# PrismTricoreVCO.net
KiCad netlist of a schematic drawn in EAGLE
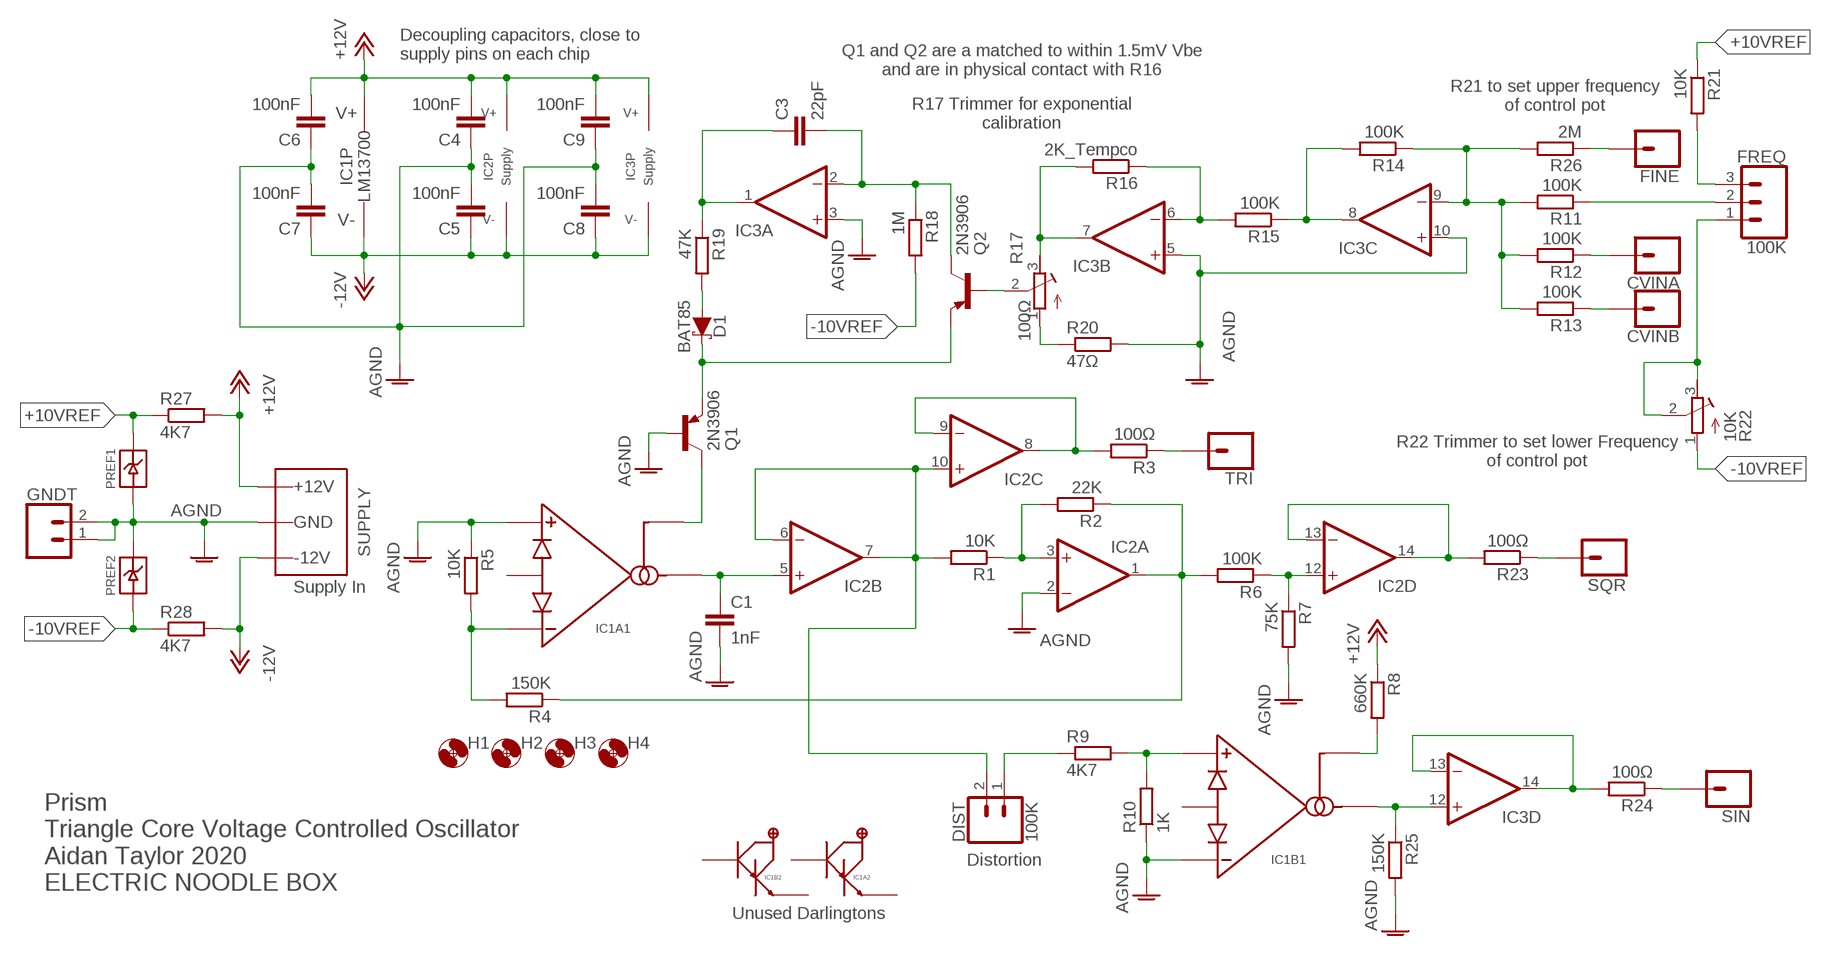
[diagram p0: schematic, sheet 1]

(export (version "E")
  (design (tool "Eeschema 10.0.6"))
  (components
    (comp (ref "C1")
      (value "1nF")
      (footprint "eagle-import:C050-025X075")
      (libsource (lib "eagle-import") (part "C-EU050-025X075"))
    )
    (comp (ref "C3")
      (value "22pF")
      (footprint "eagle-import:C050-025X075")
      (libsource (lib "eagle-import") (part "C-EU050-025X075"))
    )
    (comp (ref "C4")
      (value "100nF")
      (footprint "eagle-import:C050-025X075")
      (libsource (lib "eagle-import") (part "C-EU050-025X075"))
    )
    (comp (ref "C5")
      (value "100nF")
      (footprint "eagle-import:C050-025X075")
      (libsource (lib "eagle-import") (part "C-EU050-025X075"))
    )
    (comp (ref "C6")
      (value "100nF")
      (footprint "eagle-import:C050-025X075")
      (libsource (lib "eagle-import") (part "C-EU050-025X075"))
    )
    (comp (ref "C7")
      (value "100nF")
      (footprint "eagle-import:C050-025X075")
      (libsource (lib "eagle-import") (part "C-EU050-025X075"))
    )
    (comp (ref "C8")
      (value "100nF")
      (footprint "eagle-import:C050-025X075")
      (libsource (lib "eagle-import") (part "C-EU050-025X075"))
    )
    (comp (ref "C9")
      (value "100nF")
      (footprint "eagle-import:C050-025X075")
      (libsource (lib "eagle-import") (part "C-EU050-025X075"))
    )
    (comp (ref "CVINA")
      (value "1XWIREPAD")
      (footprint "eagle-import:1X01")
      (libsource (lib "eagle-import") (part "1XWIREPAD"))
    )
    (comp (ref "CVINB")
      (value "1XWIREPAD")
      (footprint "eagle-import:1X01")
      (libsource (lib "eagle-import") (part "1XWIREPAD"))
    )
    (comp (ref "D1")
      (value "BAT85")
      (footprint "eagle-import:DO35-7")
      (libsource (lib "eagle-import") (part "SCHOTTKY_DO35"))
    )
    (comp (ref "DIST")
      (value "100K")
      (footprint "eagle-import:1X02")
      (libsource (lib "eagle-import") (part "2XWIREPAD"))
    )
    (comp (ref "FINE")
      (value "1XWIREPAD")
      (footprint "eagle-import:1X01")
      (libsource (lib "eagle-import") (part "1XWIREPAD"))
    )
    (comp (ref "FREQ")
      (value "100K")
      (footprint "eagle-import:1X03")
      (libsource (lib "eagle-import") (part "3XWIREPAD"))
    )
    (comp (ref "GNDT")
      (value "2XWIREPAD")
      (footprint "eagle-import:1X02")
      (libsource (lib "eagle-import") (part "2XWIREPAD"))
    )
    (comp (ref "H1")
      (value "MOUNT-HOLE3.2")
      (footprint "eagle-import:3,2")
      (libsource (lib "eagle-import") (part "MOUNT-HOLE3.2"))
    )
    (comp (ref "H2")
      (value "MOUNT-HOLE3.2")
      (footprint "eagle-import:3,2")
      (libsource (lib "eagle-import") (part "MOUNT-HOLE3.2"))
    )
    (comp (ref "H3")
      (value "MOUNT-HOLE3.2")
      (footprint "eagle-import:3,2")
      (libsource (lib "eagle-import") (part "MOUNT-HOLE3.2"))
    )
    (comp (ref "H4")
      (value "MOUNT-HOLE3.2")
      (footprint "eagle-import:3,2")
      (libsource (lib "eagle-import") (part "MOUNT-HOLE3.2"))
    )
    (comp (ref "IC1")
      (value "LM13700DIL")
      (footprint "eagle-import:DIL16")
      (libsource (lib "eagle-import") (part "LM13700DIL"))
    )
    (comp (ref "IC2")
      (value "TL0X4DIL")
      (footprint "eagle-import:DIL14")
      (libsource (lib "eagle-import") (part "TL0X4DIL"))
    )
    (comp (ref "IC3")
      (value "TL0X4DIL")
      (footprint "eagle-import:DIL14")
      (libsource (lib "eagle-import") (part "TL0X4DIL"))
    )
    (comp (ref "PREF1")
      (value "LM4040TH")
      (footprint "eagle-import:TO92")
      (libsource (lib "eagle-import") (part "LM4040TH"))
    )
    (comp (ref "PREF2")
      (value "LM4040TH")
      (footprint "eagle-import:TO92")
      (libsource (lib "eagle-import") (part "LM4040TH"))
    )
    (comp (ref "Q1")
      (value "2N3906")
      (footprint "eagle-import:TO92")
      (libsource (lib "eagle-import") (part "2N3906"))
    )
    (comp (ref "Q2")
      (value "2N3906")
      (footprint "eagle-import:TO92")
      (libsource (lib "eagle-import") (part "2N3906"))
    )
    (comp (ref "R1")
      (value "10K")
      (footprint "eagle-import:0207_10")
      (libsource (lib "eagle-import") (part "R-EU_0207/10"))
    )
    (comp (ref "R2")
      (value "22K")
      (footprint "eagle-import:0207_10")
      (libsource (lib "eagle-import") (part "R-EU_0207/10"))
    )
    (comp (ref "R3")
      (value "100Ω")
      (footprint "eagle-import:0207_10")
      (libsource (lib "eagle-import") (part "R-EU_0207/10"))
    )
    (comp (ref "R4")
      (value "150K")
      (footprint "eagle-import:0207_10")
      (libsource (lib "eagle-import") (part "R-EU_0207/10"))
    )
    (comp (ref "R5")
      (value "10K")
      (footprint "eagle-import:0207_10")
      (libsource (lib "eagle-import") (part "R-EU_0207/10"))
    )
    (comp (ref "R6")
      (value "100K")
      (footprint "eagle-import:0207_10")
      (libsource (lib "eagle-import") (part "R-EU_0207/10"))
    )
    (comp (ref "R7")
      (value "75K")
      (footprint "eagle-import:0207_10")
      (libsource (lib "eagle-import") (part "R-EU_0207/10"))
    )
    (comp (ref "R8")
      (value "660K")
      (footprint "eagle-import:0207_10")
      (libsource (lib "eagle-import") (part "R-EU_0207/10"))
    )
    (comp (ref "R9")
      (value "4K7")
      (footprint "eagle-import:0207_10")
      (libsource (lib "eagle-import") (part "R-EU_0207/10"))
    )
    (comp (ref "R10")
      (value "1K")
      (footprint "eagle-import:0207_10")
      (libsource (lib "eagle-import") (part "R-EU_0207/10"))
    )
    (comp (ref "R11")
      (value "100K")
      (footprint "eagle-import:0207_10")
      (libsource (lib "eagle-import") (part "R-EU_0207/10"))
    )
    (comp (ref "R12")
      (value "100K")
      (footprint "eagle-import:0207_10")
      (libsource (lib "eagle-import") (part "R-EU_0207/10"))
    )
    (comp (ref "R13")
      (value "100K")
      (footprint "eagle-import:0207_10")
      (libsource (lib "eagle-import") (part "R-EU_0207/10"))
    )
    (comp (ref "R14")
      (value "100K")
      (footprint "eagle-import:0207_10")
      (libsource (lib "eagle-import") (part "R-EU_0207/10"))
    )
    (comp (ref "R15")
      (value "100K")
      (footprint "eagle-import:0207_10")
      (libsource (lib "eagle-import") (part "R-EU_0207/10"))
    )
    (comp (ref "R16")
      (value "2K_Tempco")
      (footprint "eagle-import:0207_10")
      (libsource (lib "eagle-import") (part "R-EU_0207/10"))
    )
    (comp (ref "R17")
      (value "100Ω")
      (footprint "eagle-import:RTRIM3296W")
      (libsource (lib "eagle-import") (part "R-TRIMM3296W"))
    )
    (comp (ref "R18")
      (value "1M")
      (footprint "eagle-import:0207_10")
      (libsource (lib "eagle-import") (part "R-EU_0207/10"))
    )
    (comp (ref "R19")
      (value "47K")
      (footprint "eagle-import:0207_10")
      (libsource (lib "eagle-import") (part "R-EU_0207/10"))
    )
    (comp (ref "R20")
      (value "47Ω")
      (footprint "eagle-import:0207_10")
      (libsource (lib "eagle-import") (part "R-EU_0207/10"))
    )
    (comp (ref "R21")
      (value "10K")
      (footprint "eagle-import:0207_10")
      (libsource (lib "eagle-import") (part "R-EU_0207/10"))
    )
    (comp (ref "R22")
      (value "10K")
      (footprint "eagle-import:RTRIM3296W")
      (libsource (lib "eagle-import") (part "R-TRIMM3296W"))
    )
    (comp (ref "R23")
      (value "100Ω")
      (footprint "eagle-import:0207_10")
      (libsource (lib "eagle-import") (part "R-EU_0207/10"))
    )
    (comp (ref "R24")
      (value "100Ω")
      (footprint "eagle-import:0207_10")
      (libsource (lib "eagle-import") (part "R-EU_0207/10"))
    )
    (comp (ref "R25")
      (value "150K")
      (footprint "eagle-import:0207_10")
      (libsource (lib "eagle-import") (part "R-EU_0207/10"))
    )
    (comp (ref "R26")
      (value "2M")
      (footprint "eagle-import:0207_10")
      (libsource (lib "eagle-import") (part "R-EU_0207/10"))
    )
    (comp (ref "R27")
      (value "4K7")
      (footprint "eagle-import:0207_10")
      (libsource (lib "eagle-import") (part "R-EU_0207/10"))
    )
    (comp (ref "R28")
      (value "4K7")
      (footprint "eagle-import:0207_10")
      (libsource (lib "eagle-import") (part "R-EU_0207/10"))
    )
    (comp (ref "SIN")
      (value "1XWIREPAD")
      (footprint "eagle-import:1X01")
      (libsource (lib "eagle-import") (part "1XWIREPAD"))
    )
    (comp (ref "SQR")
      (value "1XWIREPAD")
      (footprint "eagle-import:1X01")
      (libsource (lib "eagle-import") (part "1XWIREPAD"))
    )
    (comp (ref "TRI")
      (value "1XWIREPAD")
      (footprint "eagle-import:1X01")
      (libsource (lib "eagle-import") (part "1XWIREPAD"))
    )
    (comp (ref "WP1")
      (value "COMBO_SUPPLY_HEADER")
      (footprint "eagle-import:COMBINED_POWER")
      (libsource (lib "eagle-import") (part "COMBO_SUPPLY_HEADER"))
    )
  )
  (nets
    (net (code "1") (name "+10VREF") (class "Default")
      (node (ref "PREF1") (pin "2") (pinfunction "CATHODE_2") (pintype "power_in"))
      (node (ref "R21") (pin "1") (pinfunction "1_1") (pintype "passive"))
      (node (ref "R27") (pin "1") (pinfunction "1_1") (pintype "passive"))
    )
    (net (code "2") (name "+12V") (class "Default")
      (node (ref "C4") (pin "2") (pinfunction "2_2") (pintype "passive"))
      (node (ref "C6") (pin "2") (pinfunction "2_2") (pintype "passive"))
      (node (ref "C9") (pin "2") (pinfunction "2_2") (pintype "passive"))
      (node (ref "IC1") (pin "11") (pinfunction "V+_11") (pintype "power_in"))
      (node (ref "IC2") (pin "4") (pinfunction "V+_4") (pintype "bidirectional"))
      (node (ref "IC3") (pin "4") (pinfunction "V+_4") (pintype "bidirectional"))
      (node (ref "R27") (pin "2") (pinfunction "2_2") (pintype "passive"))
      (node (ref "R8") (pin "1") (pinfunction "1_1") (pintype "passive"))
      (node (ref "WP1") (pin "V+1") (pinfunction "V++_V+1") (pintype "power_in"))
      (node (ref "WP1") (pin "V+2") (pinfunction "V++_V+2") (pintype "power_in"))
      (node (ref "WP1") (pin "V+3") (pinfunction "V++_V+3") (pintype "power_in"))
    )
    (net (code "3") (name "-10VREF") (class "Default")
      (node (ref "PREF2") (pin "3") (pinfunction "ANODE_3") (pintype "power_in"))
      (node (ref "R18") (pin "2") (pinfunction "2_2") (pintype "passive"))
      (node (ref "R22") (pin "1") (pinfunction "A_1") (pintype "passive"))
      (node (ref "R28") (pin "1") (pinfunction "1_1") (pintype "passive"))
    )
    (net (code "4") (name "-12V") (class "Default")
      (node (ref "C5") (pin "1") (pinfunction "1_1") (pintype "passive"))
      (node (ref "C7") (pin "1") (pinfunction "1_1") (pintype "passive"))
      (node (ref "C8") (pin "1") (pinfunction "1_1") (pintype "passive"))
      (node (ref "IC1") (pin "6") (pinfunction "V-_6") (pintype "power_in"))
      (node (ref "IC2") (pin "11") (pinfunction "V-_11") (pintype "bidirectional"))
      (node (ref "IC3") (pin "11") (pinfunction "V-_11") (pintype "bidirectional"))
      (node (ref "R28") (pin "2") (pinfunction "2_2") (pintype "passive"))
      (node (ref "WP1") (pin "V-1") (pinfunction "V--_V-1") (pintype "power_in"))
      (node (ref "WP1") (pin "V-2") (pinfunction "V--_V-2") (pintype "power_in"))
      (node (ref "WP1") (pin "V-3") (pinfunction "V--_V-3") (pintype "power_in"))
    )
    (net (code "5") (name "AGND") (class "Default")
      (node (ref "C1") (pin "2") (pinfunction "2_2") (pintype "passive"))
      (node (ref "C4") (pin "1") (pinfunction "1_1") (pintype "passive"))
      (node (ref "C5") (pin "2") (pinfunction "2_2") (pintype "passive"))
      (node (ref "C6") (pin "1") (pinfunction "1_1") (pintype "passive"))
      (node (ref "C7") (pin "2") (pinfunction "2_2") (pintype "passive"))
      (node (ref "C8") (pin "2") (pinfunction "2_2") (pintype "passive"))
      (node (ref "C9") (pin "1") (pinfunction "1_1") (pintype "passive"))
      (node (ref "GNDT") (pin "1") (pinfunction "1_1") (pintype "passive"))
      (node (ref "GNDT") (pin "2") (pinfunction "2_2") (pintype "passive"))
      (node (ref "IC1") (pin "13") (pinfunction "AMP-_13") (pintype "input"))
      (node (ref "IC1") (pin "3") (pinfunction "AMP+_3") (pintype "input"))
      (node (ref "IC2") (pin "2") (pinfunction "-IN_2") (pintype "input"))
      (node (ref "IC3") (pin "10") (pinfunction "+IN_10") (pintype "input"))
      (node (ref "IC3") (pin "3") (pinfunction "+IN_3") (pintype "input"))
      (node (ref "IC3") (pin "5") (pinfunction "+IN_5") (pintype "input"))
      (node (ref "PREF1") (pin "3") (pinfunction "ANODE_3") (pintype "power_in"))
      (node (ref "PREF2") (pin "2") (pinfunction "CATHODE_2") (pintype "power_in"))
      (node (ref "Q1") (pin "2") (pinfunction "B_2") (pintype "passive"))
      (node (ref "R10") (pin "1") (pinfunction "1_1") (pintype "passive"))
      (node (ref "R20") (pin "2") (pinfunction "2_2") (pintype "passive"))
      (node (ref "R25") (pin "2") (pinfunction "2_2") (pintype "passive"))
      (node (ref "R5") (pin "1") (pinfunction "1_1") (pintype "passive"))
      (node (ref "R7") (pin "2") (pinfunction "2_2") (pintype "passive"))
      (node (ref "WP1") (pin "GND1") (pinfunction "AGND_GND1") (pintype "power_in"))
      (node (ref "WP1") (pin "GND2") (pinfunction "AGND_GND2") (pintype "power_in"))
      (node (ref "WP1") (pin "GND3") (pinfunction "AGND_GND3") (pintype "power_in"))
      (node (ref "WP1") (pin "GND4") (pinfunction "AGND_GND4") (pintype "power_in"))
      (node (ref "WP1") (pin "GND5") (pinfunction "AGND_GND5") (pintype "power_in"))
      (node (ref "WP1") (pin "GND6") (pinfunction "AGND_GND6") (pintype "power_in"))
      (node (ref "WP1") (pin "GND7") (pinfunction "AGND_GND7") (pintype "power_in"))
      (node (ref "WP1") (pin "GND8") (pinfunction "AGND_GND8") (pintype "power_in"))
    )
    (net (code "6") (name "Net-(CVINA-Pad1)") (class "Default")
      (node (ref "CVINA") (pin "1") (pinfunction "1_1") (pintype "passive"))
      (node (ref "R12") (pin "1") (pinfunction "1_1") (pintype "passive"))
    )
    (net (code "7") (name "Net-(CVINB-Pad1)") (class "Default")
      (node (ref "CVINB") (pin "1") (pinfunction "1_1") (pintype "passive"))
      (node (ref "R13") (pin "1") (pinfunction "1_1") (pintype "passive"))
    )
    (net (code "8") (name "Net-(D1-PadA)") (class "Default")
      (node (ref "D1") (pin "A") (pinfunction "A_A") (pintype "passive"))
      (node (ref "R19") (pin "2") (pinfunction "2_2") (pintype "passive"))
    )
    (net (code "9") (name "Net-(DIST-Pad1)") (class "Default")
      (node (ref "DIST") (pin "1") (pinfunction "1_1") (pintype "passive"))
      (node (ref "R9") (pin "1") (pinfunction "1_1") (pintype "passive"))
    )
    (net (code "10") (name "Net-(FINE-Pad1)") (class "Default")
      (node (ref "FINE") (pin "1") (pinfunction "1_1") (pintype "passive"))
      (node (ref "R26") (pin "1") (pinfunction "1_1") (pintype "passive"))
    )
    (net (code "11") (name "Net-(FREQ-Pad2)") (class "Default")
      (node (ref "FREQ") (pin "2") (pinfunction "2_2") (pintype "passive"))
      (node (ref "R11") (pin "1") (pinfunction "1_1") (pintype "passive"))
    )
    (net (code "12") (name "Net-(FREQ-Pad3)") (class "Default")
      (node (ref "FREQ") (pin "3") (pinfunction "3_3") (pintype "passive"))
      (node (ref "R21") (pin "2") (pinfunction "2_2") (pintype "passive"))
    )
    (net (code "13") (name "Net-(IC1A-AMP-)") (class "Default")
      (node (ref "IC1") (pin "4") (pinfunction "AMP-_4") (pintype "input"))
      (node (ref "R4") (pin "2") (pinfunction "2_2") (pintype "passive"))
      (node (ref "R5") (pin "2") (pinfunction "2_2") (pintype "passive"))
    )
    (net (code "14") (name "Net-(IC1A-AMPBIAS)") (class "Default")
      (node (ref "IC1") (pin "1") (pinfunction "AMPBIAS_1") (pintype "input"))
      (node (ref "Q1") (pin "1") (pinfunction "C_1") (pintype "passive"))
    )
    (net (code "15") (name "Net-(IC1A-AMPOUT)") (class "Default")
      (node (ref "C1") (pin "1") (pinfunction "1_1") (pintype "passive"))
      (node (ref "IC1") (pin "5") (pinfunction "AMPOUT_5") (pintype "output"))
      (node (ref "IC2") (pin "5") (pinfunction "+IN_5") (pintype "input"))
    )
    (net (code "16") (name "Net-(IC1C-AMP+)") (class "Default")
      (node (ref "IC1") (pin "14") (pinfunction "AMP+_14") (pintype "input"))
      (node (ref "R10") (pin "2") (pinfunction "2_2") (pintype "passive"))
      (node (ref "R9") (pin "2") (pinfunction "2_2") (pintype "passive"))
    )
    (net (code "17") (name "Net-(IC1C-AMPBIAS)") (class "Default")
      (node (ref "IC1") (pin "16") (pinfunction "AMPBIAS_16") (pintype "input"))
      (node (ref "R8") (pin "2") (pinfunction "2_2") (pintype "passive"))
    )
    (net (code "18") (name "Net-(IC1C-AMPOUT)") (class "Default")
      (node (ref "IC1") (pin "12") (pinfunction "AMPOUT_12") (pintype "output"))
      (node (ref "IC3") (pin "12") (pinfunction "+IN_12") (pintype "input"))
      (node (ref "R25") (pin "1") (pinfunction "1_1") (pintype "passive"))
    )
    (net (code "19") (name "Net-(IC2A-+IN)") (class "Default")
      (node (ref "IC2") (pin "3") (pinfunction "+IN_3") (pintype "input"))
      (node (ref "R1") (pin "1") (pinfunction "1_1") (pintype "passive"))
      (node (ref "R2") (pin "2") (pinfunction "2_2") (pintype "passive"))
    )
    (net (code "20") (name "Net-(IC2A-OUT)") (class "Default")
      (node (ref "IC2") (pin "1") (pinfunction "OUT_1") (pintype "output"))
      (node (ref "R2") (pin "1") (pinfunction "1_1") (pintype "passive"))
      (node (ref "R4") (pin "1") (pinfunction "1_1") (pintype "passive"))
      (node (ref "R6") (pin "2") (pinfunction "2_2") (pintype "passive"))
    )
    (net (code "21") (name "Net-(IC2B--IN)") (class "Default")
      (node (ref "DIST") (pin "2") (pinfunction "2_2") (pintype "passive"))
      (node (ref "IC2") (pin "10") (pinfunction "+IN_10") (pintype "input"))
      (node (ref "IC2") (pin "6") (pinfunction "-IN_6") (pintype "input"))
      (node (ref "IC2") (pin "7") (pinfunction "OUT_7") (pintype "output"))
      (node (ref "R1") (pin "2") (pinfunction "2_2") (pintype "passive"))
    )
    (net (code "22") (name "Net-(IC2C--IN)") (class "Default")
      (node (ref "IC2") (pin "8") (pinfunction "OUT_8") (pintype "output"))
      (node (ref "IC2") (pin "9") (pinfunction "-IN_9") (pintype "input"))
      (node (ref "R3") (pin "2") (pinfunction "2_2") (pintype "passive"))
    )
    (net (code "23") (name "Net-(IC2D-+IN)") (class "Default")
      (node (ref "IC2") (pin "12") (pinfunction "+IN_12") (pintype "input"))
      (node (ref "R6") (pin "1") (pinfunction "1_1") (pintype "passive"))
      (node (ref "R7") (pin "1") (pinfunction "1_1") (pintype "passive"))
    )
    (net (code "24") (name "Net-(IC2D--IN)") (class "Default")
      (node (ref "IC2") (pin "13") (pinfunction "-IN_13") (pintype "input"))
      (node (ref "IC2") (pin "14") (pinfunction "OUT_14") (pintype "output"))
      (node (ref "R23") (pin "2") (pinfunction "2_2") (pintype "passive"))
    )
    (net (code "25") (name "Net-(IC3A--IN)") (class "Default")
      (node (ref "C3") (pin "2") (pinfunction "2_2") (pintype "passive"))
      (node (ref "IC3") (pin "2") (pinfunction "-IN_2") (pintype "input"))
      (node (ref "Q2") (pin "1") (pinfunction "C_1") (pintype "passive"))
      (node (ref "R18") (pin "1") (pinfunction "1_1") (pintype "passive"))
    )
    (net (code "26") (name "Net-(IC3A-OUT)") (class "Default")
      (node (ref "C3") (pin "1") (pinfunction "1_1") (pintype "passive"))
      (node (ref "IC3") (pin "1") (pinfunction "OUT_1") (pintype "output"))
      (node (ref "R19") (pin "1") (pinfunction "1_1") (pintype "passive"))
    )
    (net (code "27") (name "Net-(IC3B--IN)") (class "Default")
      (node (ref "IC3") (pin "6") (pinfunction "-IN_6") (pintype "input"))
      (node (ref "R15") (pin "2") (pinfunction "2_2") (pintype "passive"))
      (node (ref "R16") (pin "1") (pinfunction "1_1") (pintype "passive"))
    )
    (net (code "28") (name "Net-(IC3B-OUT)") (class "Default")
      (node (ref "IC3") (pin "7") (pinfunction "OUT_7") (pintype "output"))
      (node (ref "R16") (pin "2") (pinfunction "2_2") (pintype "passive"))
      (node (ref "R17") (pin "3") (pinfunction "E_3") (pintype "passive"))
    )
    (net (code "29") (name "Net-(IC3C--IN)") (class "Default")
      (node (ref "IC3") (pin "9") (pinfunction "-IN_9") (pintype "input"))
      (node (ref "R11") (pin "2") (pinfunction "2_2") (pintype "passive"))
      (node (ref "R12") (pin "2") (pinfunction "2_2") (pintype "passive"))
      (node (ref "R13") (pin "2") (pinfunction "2_2") (pintype "passive"))
      (node (ref "R14") (pin "1") (pinfunction "1_1") (pintype "passive"))
      (node (ref "R26") (pin "2") (pinfunction "2_2") (pintype "passive"))
    )
    (net (code "30") (name "Net-(IC3C-OUT)") (class "Default")
      (node (ref "IC3") (pin "8") (pinfunction "OUT_8") (pintype "output"))
      (node (ref "R14") (pin "2") (pinfunction "2_2") (pintype "passive"))
      (node (ref "R15") (pin "1") (pinfunction "1_1") (pintype "passive"))
    )
    (net (code "31") (name "Net-(IC3D--IN)") (class "Default")
      (node (ref "IC3") (pin "13") (pinfunction "-IN_13") (pintype "input"))
      (node (ref "IC3") (pin "14") (pinfunction "OUT_14") (pintype "output"))
      (node (ref "R24") (pin "2") (pinfunction "2_2") (pintype "passive"))
    )
    (net (code "32") (name "Net-(Q1-E)") (class "Default")
      (node (ref "D1") (pin "C") (pinfunction "C_C") (pintype "passive"))
      (node (ref "Q1") (pin "3") (pinfunction "E_3") (pintype "passive"))
      (node (ref "Q2") (pin "3") (pinfunction "E_3") (pintype "passive"))
    )
    (net (code "33") (name "Net-(Q2-B)") (class "Default")
      (node (ref "Q2") (pin "2") (pinfunction "B_2") (pintype "passive"))
      (node (ref "R17") (pin "2") (pinfunction "S_2") (pintype "passive"))
    )
    (net (code "34") (name "Net-(R3-Pad1)") (class "Default")
      (node (ref "R3") (pin "1") (pinfunction "1_1") (pintype "passive"))
      (node (ref "TRI") (pin "1") (pinfunction "1_1") (pintype "passive"))
    )
    (net (code "35") (name "Net-(R17-A)") (class "Default")
      (node (ref "R17") (pin "1") (pinfunction "A_1") (pintype "passive"))
      (node (ref "R20") (pin "1") (pinfunction "1_1") (pintype "passive"))
    )
    (net (code "36") (name "Net-(R22-E)") (class "Default")
      (node (ref "FREQ") (pin "1") (pinfunction "1_1") (pintype "passive"))
      (node (ref "R22") (pin "2") (pinfunction "S_2") (pintype "passive"))
      (node (ref "R22") (pin "3") (pinfunction "E_3") (pintype "passive"))
    )
    (net (code "37") (name "Net-(R23-Pad1)") (class "Default")
      (node (ref "R23") (pin "1") (pinfunction "1_1") (pintype "passive"))
      (node (ref "SQR") (pin "1") (pinfunction "1_1") (pintype "passive"))
    )
    (net (code "38") (name "Net-(R24-Pad1)") (class "Default")
      (node (ref "R24") (pin "1") (pinfunction "1_1") (pintype "passive"))
      (node (ref "SIN") (pin "1") (pinfunction "1_1") (pintype "passive"))
    )
    (net (code "39") (name "unconnected-(IC1A-DIODES-Pad2)") (class "Default")
      (node (ref "IC1") (pin "2") (pinfunction "DIODES_2") (pintype "input"))
    )
    (net (code "40") (name "unconnected-(IC1B-BUFF_IN-Pad7)") (class "Default")
      (node (ref "IC1") (pin "7") (pinfunction "BUFF_IN_7") (pintype "input"))
    )
    (net (code "41") (name "unconnected-(IC1B-BUFF_OUT-Pad8)") (class "Default")
      (node (ref "IC1") (pin "8") (pinfunction "BUFF_OUT_8") (pintype "bidirectional"))
    )
    (net (code "42") (name "unconnected-(IC1C-DIODES-Pad15)") (class "Default")
      (node (ref "IC1") (pin "15") (pinfunction "DIODES_15") (pintype "input"))
    )
    (net (code "43") (name "unconnected-(IC1D-BUFF_IN-Pad10)") (class "Default")
      (node (ref "IC1") (pin "10") (pinfunction "BUFF_IN_10") (pintype "input"))
    )
    (net (code "44") (name "unconnected-(IC1D-BUFF_OUT-Pad9)") (class "Default")
      (node (ref "IC1") (pin "9") (pinfunction "BUFF_OUT_9") (pintype "bidirectional"))
    )
  )
)
